# Boost_Converter_Circuit.net
KiCad netlist of a schematic drawn in Altium Designer
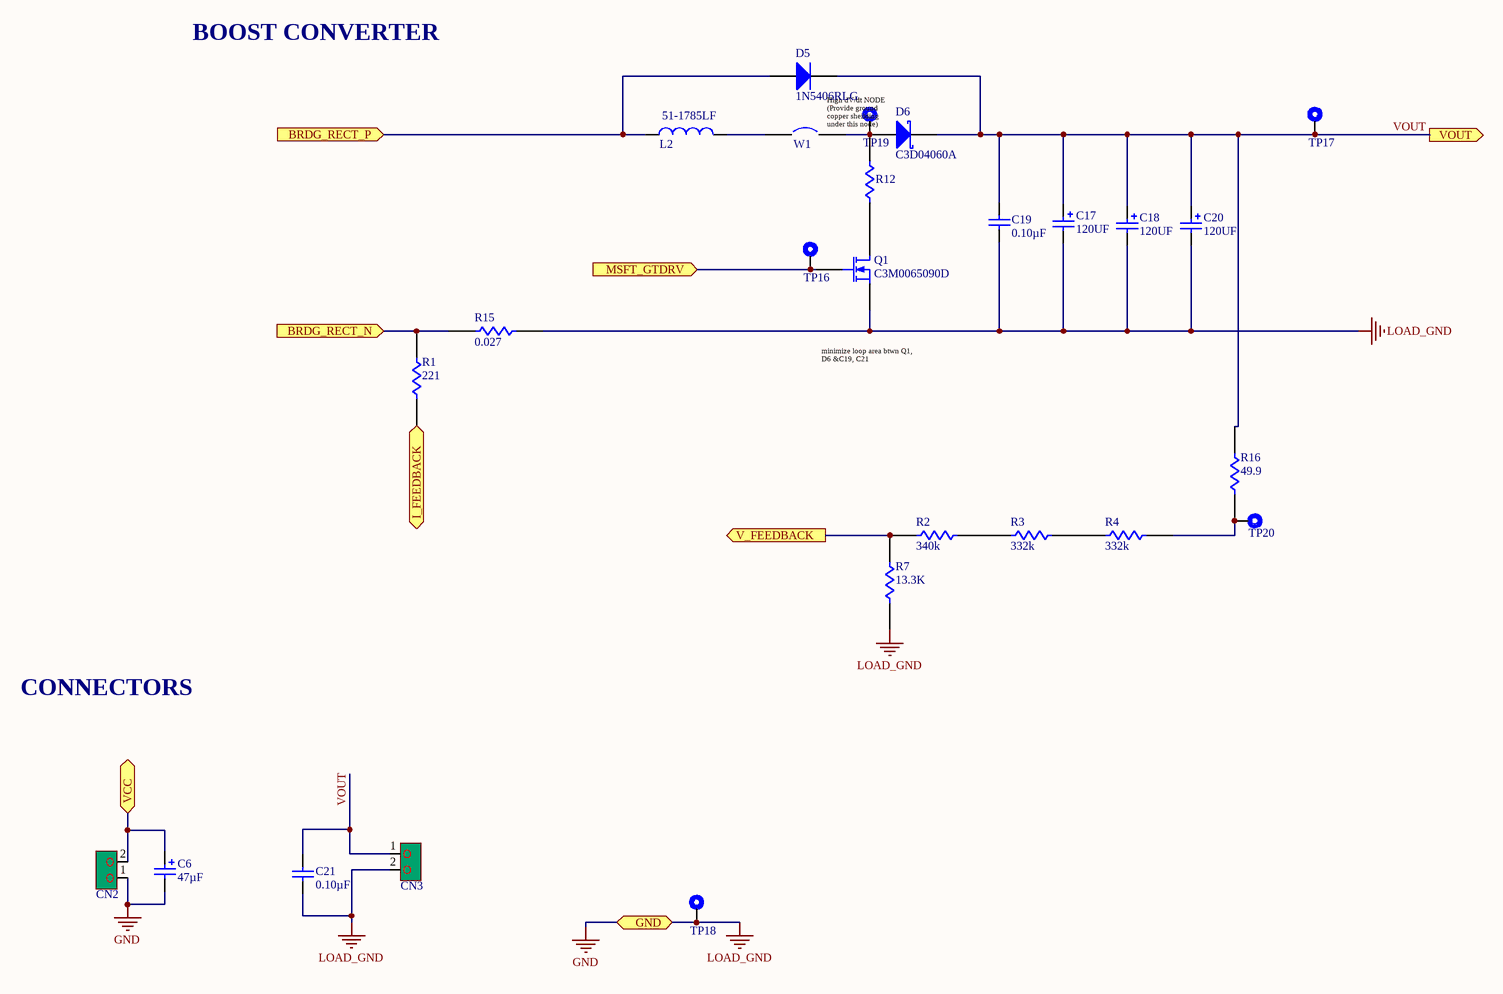
[diagram p0: Boost Converter Circuit.SchDoc]

(export (version "E")
  (design (tool "Eeschema 10.0.6"))
  (components
    (comp (ref "C6")
      (value "ECA-1VM470")
      (footprint "CAPALUM47U")
      (description "CAP ALUM 47UF 20% 35V RADIAL")
      (fields (field (name "TOLERANCE") "±20%") (field (name "CAPACITANCE") "47µF"))
      (libsource (lib "ucc28180") (part "ECA-1VM470"))
    )
    (comp (ref "C17")
      (value "450QXW120MEFC18X31.5")
      (footprint "450QXW120MEFC18X31.5")
      (fields (field (name "CAPACITANCE") "120UF"))
      (libsource (lib "ucc28180") (part "450QXW120MEFC18X31.5"))
    )
    (comp (ref "C18")
      (value "450QXW120MEFC18X31.5")
      (footprint "450QXW120MEFC18X31.5")
      (fields (field (name "CAPACITANCE") "120UF"))
      (libsource (lib "ucc28180") (part "450QXW120MEFC18X31.5"))
    )
    (comp (ref "C19")
      (value "GRM43DR72J104KW01L")
      (footprint "CAP1812")
      (description "CAP CER 0.1UF 630V X7R 1812")
      (fields (field (name "TOLERANCE") "±10%") (field (name "CAPACITANCE") "0.10µF"))
      (libsource (lib "ucc28180") (part "GRM43DR72J104KW01L"))
    )
    (comp (ref "C20")
      (value "450QXW120MEFC18X31.5")
      (footprint "450QXW120MEFC18X31.5")
      (fields (field (name "CAPACITANCE") "120UF"))
      (libsource (lib "ucc28180") (part "450QXW120MEFC18X31.5"))
    )
    (comp (ref "C21")
      (value "GRM43DR72J104KW01L")
      (footprint "CAP1812")
      (description "CAP CER 0.1UF 630V X7R 1812")
      (fields (field (name "TOLERANCE") "±10%") (field (name "CAPACITANCE") "0.10µF"))
      (libsource (lib "ucc28180") (part "GRM43DR72J104KW01L"))
    )
    (comp (ref "CN2")
      (value "1935776")
      (footprint "CONN_1935776")
      (description "CONN TERM BLOCK 2POS 5.0MM")
      (fields (field (name "VOLTAGE") "300V"))
      (libsource (lib "") (part "1935776_1"))
    )
    (comp (ref "CN3")
      (value "1935776")
      (footprint "CONN_1935776")
      (description "CONN TERM BLOCK 2POS 5.0MM")
      (fields (field (name "VOLTAGE") "300V"))
      (libsource (lib "ucc28180") (part "1935776"))
    )
    (comp (ref "D5")
      (value "1N5406RLG")
      (footprint "1N5406-DO201AD")
      (description "DIODE GEN PURP 600V 3A DO201AD")
      (fields
        (field (name "MANUFACTURER") "ON Semiconductor")
        (field (name "MANUFACTURER PART NUMBER") "1N5406RLG")
      )
      (libsource (lib "ucc28180-V03") (part "1N5406RLG"))
    )
    (comp (ref "D6")
      (value "C3D04060A")
      (footprint "C3D04060A")
      (description "DIODE SCHOTTKY 600V 4A TO220-2")
      (fields (field (name "MANUFACTURER PART NUMBER 1") "C3D04060A"))
      (libsource (lib "ucc28180") (part "C3D04060A"))
    )
    (comp (ref "L2")
      (value "51-1785LF")
      (footprint "G-51-185LF")
      (fields (field (name "MANUFACTURER") "Gowanda Electronics"))
      (libsource (lib "ucc28180-V02") (part "51-1785LF"))
    )
    (comp (ref "Q1")
      (value "C3M0065090D")
      (footprint "TO-247-3")
      (description "MOSFET N-CH 900V 36A TO247-3")
      (fields (field (name "MANUFACTURER PART NUMBER 1") "C3M0065090D"))
      (libsource (lib "ucc28180-V02") (part "C3M0065090D"))
    )
    (comp (ref "R1")
      (value "CRCW0603221RFKEA")
      (footprint "RES0603")
      (description "RES SMD 221 OHM 1% 1/10W 0603")
      (fields (field (name "TOLERANCE") "±1%") (field (name "RESISTANCE (OHMS)") "221"))
      (libsource (lib "ucc28180-V03") (part "CRCW0603221RFKEA"))
    )
    (comp (ref "R2")
      (value "CRCW0805340KFKEA")
      (footprint "RES0805")
      (description "RES SMD 340K OHM 1% 1/8W 0805")
      (fields (field (name "TOLERANCE") "±1%") (field (name "RESISTANCE (OHMS)") "340k"))
      (libsource (lib "ucc28180") (part "CRCW0805340KFKEA"))
    )
    (comp (ref "R3")
      (value "CRCW0805332KFKEA")
      (footprint "RES0805")
      (description "RES SMD 332K OHM 1% 1/8W 0805")
      (fields (field (name "TOLERANCE") "±1%") (field (name "RESISTANCE (OHMS)") "332k"))
      (libsource (lib "ucc28180") (part "CRCW0805332KFKEA"))
    )
    (comp (ref "R4")
      (value "CRCW0805332KFKEA")
      (footprint "RES0805")
      (description "RES SMD 332K OHM 1% 1/8W 0805")
      (fields (field (name "TOLERANCE") "±1%") (field (name "RESISTANCE (OHMS)") "332k"))
      (libsource (lib "ucc28180") (part "CRCW0805332KFKEA"))
    )
    (comp (ref "R7")
      (value "CRCW060313K3FKEA")
      (footprint "RES0603")
      (description "RES SMD 13.3K OHM 1% 1/10W 0603")
      (fields (field (name "TOLERANCE") "±1%") (field (name "RESISTANCE") "13.3K"))
      (libsource (lib "ucc28180") (part "CRCW060313K3FKEA"))
    )
    (comp (ref "R12")
      (value "CRCWRSHUNT")
      (footprint "Wire-Sense")
      (libsource (lib "ucc28180") (part "CRCWRSHUNT"))
    )
    (comp (ref "R15")
      (value "CRCW2512R0.027")
      (footprint "RES2512")
      (fields (field (name "RESISTANCE") "0.027"))
      (libsource (lib "ucc28180") (part "CRCW2512R0.027"))
    )
    (comp (ref "R16")
      (value "CRCW120649R9FKEA")
      (footprint "RES1206")
      (description "RES SMD 49.9 OHM 1% 1/4W 1206")
      (fields (field (name "TOLERANCE") "±1%") (field (name "RESISTANCE (OHMS)") "49.9"))
      (libsource (lib "ucc28180") (part "CRCW120649R9FKEA"))
    )
    (comp (ref "TP16")
      (value "5006")
      (footprint "Test Point")
      (description "TEST POINT PC COMPACT .063\"D BLK")
      (libsource (lib "ucc28180") (part "5006"))
    )
    (comp (ref "TP17")
      (value "5006")
      (footprint "Test Point")
      (description "TEST POINT PC COMPACT .063\"D BLK")
      (libsource (lib "ucc28180") (part "5006"))
    )
    (comp (ref "TP18")
      (value "5006")
      (footprint "Test Point")
      (description "TEST POINT PC COMPACT .063\"D BLK")
      (libsource (lib "ucc28180") (part "5006"))
    )
    (comp (ref "TP19")
      (value "5006")
      (footprint "Test Point")
      (description "TEST POINT PC COMPACT .063\"D BLK")
      (libsource (lib "ucc28180") (part "5006"))
    )
    (comp (ref "TP20")
      (value "5006")
      (footprint "Test Point")
      (description "TEST POINT PC COMPACT .063\"D BLK")
      (libsource (lib "ucc28180") (part "5006"))
    )
    (comp (ref "W1")
      (value "Wire")
      (footprint "Current Sense Wire")
      (libsource (lib "ucc28180-V02") (part "Wire"))
    )
  )
  (nets
    (net (code "1") (name "/BRDG_RECT_N") (class "Default")
      (node (ref "R1") (pin "1") (pinfunction "1_1") (pintype "passive"))
      (node (ref "R15") (pin "2") (pinfunction "2_2") (pintype "passive"))
    )
    (net (code "2") (name "/BRDG_RECT_P") (class "Default")
      (node (ref "D5") (pin "2") (pinfunction "A_2") (pintype "passive"))
      (node (ref "L2") (pin "1") (pinfunction "1_1") (pintype "passive"))
    )
    (net (code "3") (name "/I_FEEDBACK") (class "Default")
      (node (ref "R1") (pin "2") (pinfunction "2_2") (pintype "passive"))
    )
    (net (code "4") (name "/MSFT_GTDRV") (class "Default")
      (node (ref "Q1") (pin "1") (pinfunction "G_1") (pintype "passive"))
      (node (ref "TP16") (pin "1") (pinfunction "1_1") (pintype "passive"))
    )
    (net (code "5") (name "/VCC") (class "Default")
      (node (ref "C6") (pin "1") (pinfunction "1_1") (pintype "passive"))
      (node (ref "CN2") (pin "2") (pintype "passive"))
    )
    (net (code "6") (name "/VOUT") (class "Default")
      (node (ref "C17") (pin "1") (pinfunction "1_1") (pintype "passive"))
      (node (ref "C18") (pin "1") (pinfunction "1_1") (pintype "passive"))
      (node (ref "C19") (pin "2") (pinfunction "2_2") (pintype "passive"))
      (node (ref "C20") (pin "1") (pinfunction "1_1") (pintype "passive"))
      (node (ref "C21") (pin "2") (pinfunction "2_2") (pintype "passive"))
      (node (ref "CN3") (pin "1") (pintype "passive"))
      (node (ref "D5") (pin "1") (pinfunction "K_1") (pintype "passive"))
      (node (ref "D6") (pin "1") (pinfunction "K_1") (pintype "passive"))
      (node (ref "R16") (pin "1") (pinfunction "1_1") (pintype "passive"))
      (node (ref "TP17") (pin "1") (pinfunction "1_1") (pintype "passive"))
    )
    (net (code "7") (name "/V_FEEDBACK") (class "Default")
      (node (ref "R2") (pin "2") (pinfunction "2_2") (pintype "passive"))
      (node (ref "R7") (pin "1") (pinfunction "1_1") (pintype "passive"))
    )
    (net (code "8") (name "GND") (class "Default")
      (node (ref "C17") (pin "2") (pinfunction "2_2") (pintype "passive"))
      (node (ref "C18") (pin "2") (pinfunction "2_2") (pintype "passive"))
      (node (ref "C19") (pin "1") (pinfunction "1_1") (pintype "passive"))
      (node (ref "C20") (pin "2") (pinfunction "2_2") (pintype "passive"))
      (node (ref "C21") (pin "1") (pinfunction "1_1") (pintype "passive"))
      (node (ref "C6") (pin "2") (pinfunction "2_2") (pintype "passive"))
      (node (ref "CN2") (pin "1") (pintype "passive"))
      (node (ref "CN3") (pin "2") (pintype "passive"))
      (node (ref "Q1") (pin "3") (pinfunction "S_3") (pintype "passive"))
      (node (ref "R15") (pin "1") (pinfunction "1_1") (pintype "passive"))
      (node (ref "R7") (pin "2") (pinfunction "2_2") (pintype "passive"))
      (node (ref "TP18") (pin "1") (pinfunction "1_1") (pintype "passive"))
    )
    (net (code "9") (name "Net-(D6-A)") (class "Default")
      (node (ref "D6") (pin "2") (pinfunction "A_2") (pintype "passive"))
      (node (ref "R12") (pin "1") (pinfunction "1_1") (pintype "passive"))
      (node (ref "TP19") (pin "1") (pinfunction "1_1") (pintype "passive"))
      (node (ref "W1") (pin "2") (pinfunction "2_2") (pintype "passive"))
    )
    (net (code "10") (name "Net-(L2-Pad2)") (class "Default")
      (node (ref "L2") (pin "2") (pinfunction "2_2") (pintype "passive"))
      (node (ref "W1") (pin "1") (pinfunction "1_1") (pintype "passive"))
    )
    (net (code "11") (name "Net-(Q1-D)") (class "Default")
      (node (ref "Q1") (pin "2") (pinfunction "D_2") (pintype "passive"))
      (node (ref "R12") (pin "2") (pinfunction "2_2") (pintype "passive"))
    )
    (net (code "12") (name "Net-(R2-Pad1)") (class "Default")
      (node (ref "R2") (pin "1") (pinfunction "1_1") (pintype "passive"))
      (node (ref "R3") (pin "2") (pinfunction "2_2") (pintype "passive"))
    )
    (net (code "13") (name "Net-(R3-Pad1)") (class "Default")
      (node (ref "R3") (pin "1") (pinfunction "1_1") (pintype "passive"))
      (node (ref "R4") (pin "2") (pinfunction "2_2") (pintype "passive"))
    )
    (net (code "14") (name "Net-(R16-Pad2)") (class "Default")
      (node (ref "R16") (pin "2") (pinfunction "2_2") (pintype "passive"))
      (node (ref "R4") (pin "1") (pinfunction "1_1") (pintype "passive"))
      (node (ref "TP20") (pin "1") (pinfunction "1_1") (pintype "passive"))
    )
  )
)
